# current_mirror.net
KiCad netlist of a schematic drawn in EAGLE
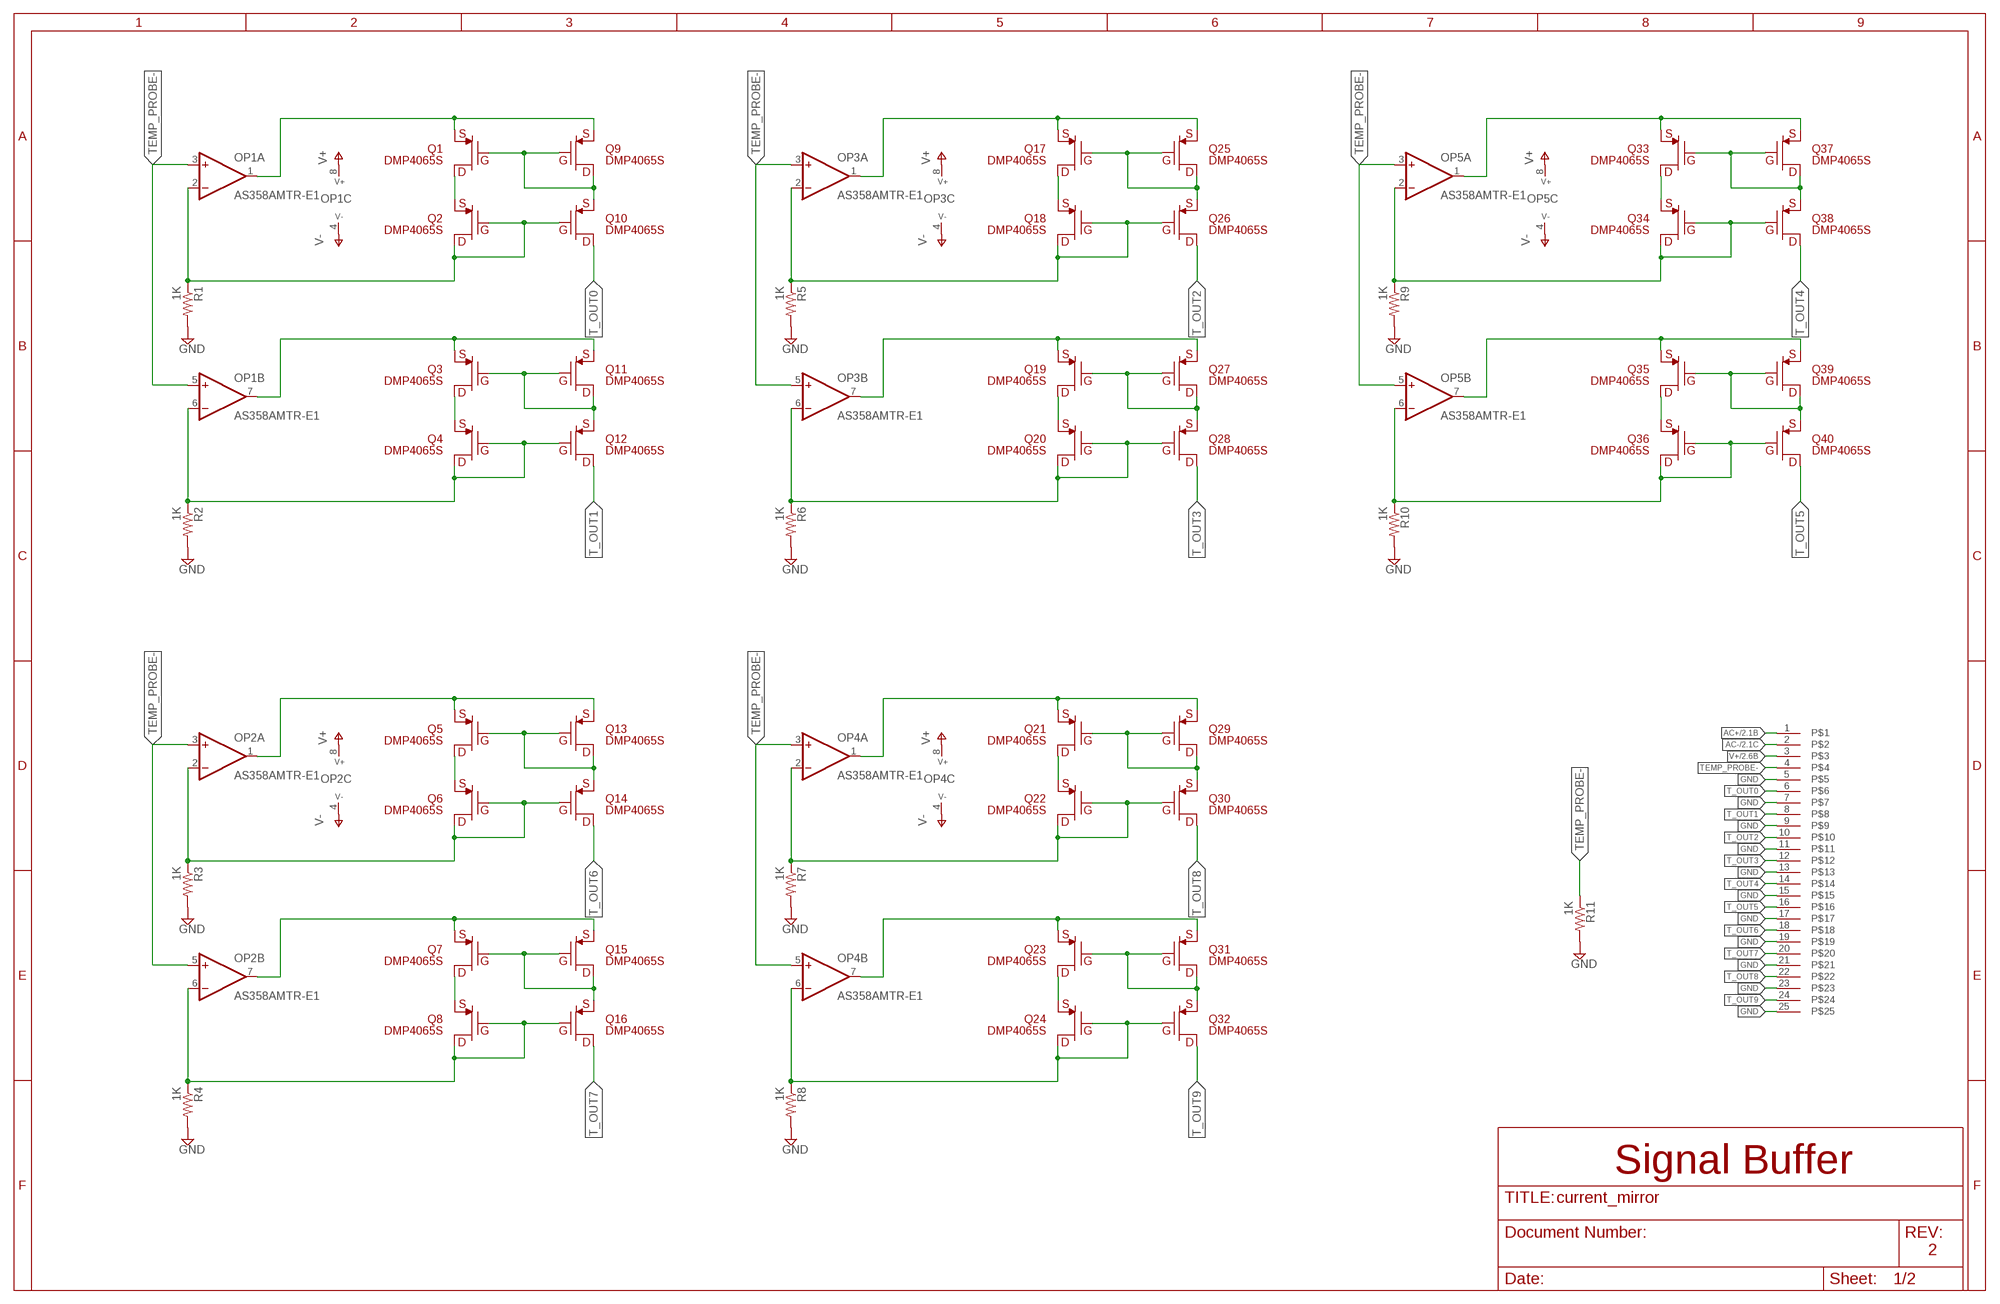
[diagram p0: schematic, sheet 1]
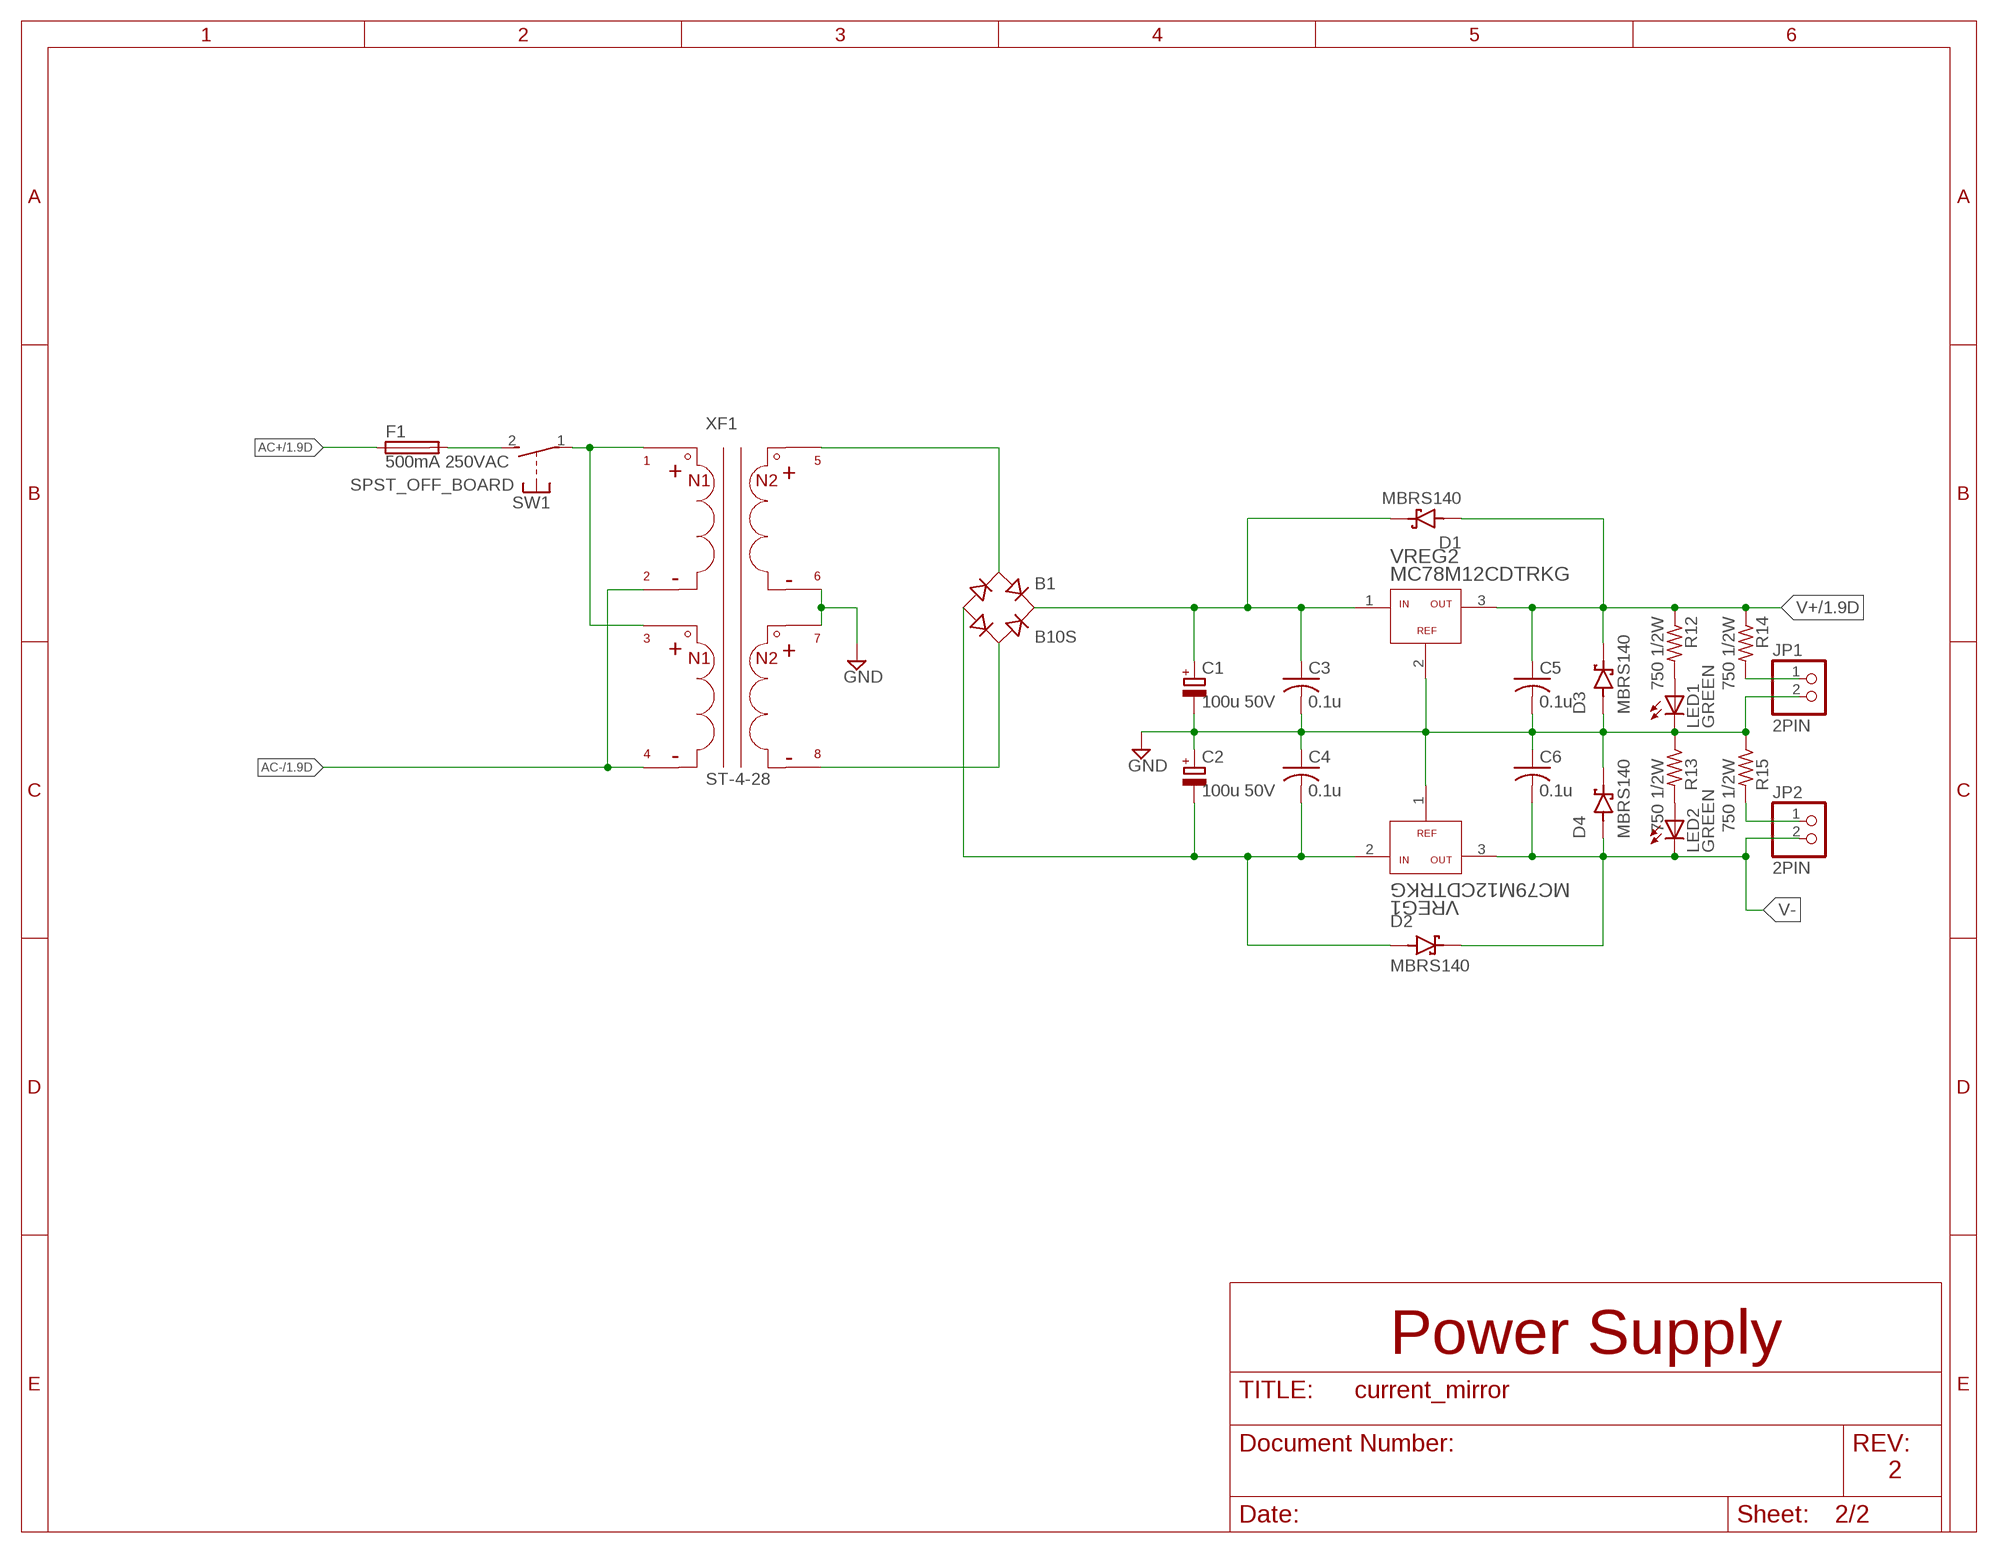
[diagram p1: schematic, sheet 2]

(export (version "E")
  (design (tool "Eeschema 10.0.6"))
  (components
    (comp (ref "J1")
      (value "2-282836-6")
      (footprint "eagle-import:SCREW_TERMINAL_25")
      (libsource (lib "eagle-import") (part "2-282836-6"))
    )
    (comp (ref "OP1")
      (value "AS358AMTR-E1")
      (footprint "eagle-import:SOIC-8")
      (fields (field (name "JLCPCB_PART_NUMBER") "C141322"))
      (libsource (lib "eagle-import") (part "AS358AMTR-E1"))
    )
    (comp (ref "OP2")
      (value "AS358AMTR-E1")
      (footprint "eagle-import:SOIC-8")
      (fields (field (name "JLCPCB_PART_NUMBER") "C141322"))
      (libsource (lib "eagle-import") (part "AS358AMTR-E1"))
    )
    (comp (ref "OP3")
      (value "AS358AMTR-E1")
      (footprint "eagle-import:SOIC-8")
      (fields (field (name "JLCPCB_PART_NUMBER") "C141322"))
      (libsource (lib "eagle-import") (part "AS358AMTR-E1"))
    )
    (comp (ref "OP4")
      (value "AS358AMTR-E1")
      (footprint "eagle-import:SOIC-8")
      (fields (field (name "JLCPCB_PART_NUMBER") "C141322"))
      (libsource (lib "eagle-import") (part "AS358AMTR-E1"))
    )
    (comp (ref "OP5")
      (value "AS358AMTR-E1")
      (footprint "eagle-import:SOIC-8")
      (fields (field (name "JLCPCB_PART_NUMBER") "C141322"))
      (libsource (lib "eagle-import") (part "AS358AMTR-E1"))
    )
    (comp (ref "Q1")
      (value "DMP4065S")
      (footprint "eagle-import:SOT23")
      (fields (field (name "JLCPCB_PART_NUMBER") "C182476"))
      (libsource (lib "eagle-import") (part "DMP4065S"))
    )
    (comp (ref "Q2")
      (value "DMP4065S")
      (footprint "eagle-import:SOT23")
      (fields (field (name "JLCPCB_PART_NUMBER") "C182476"))
      (libsource (lib "eagle-import") (part "DMP4065S"))
    )
    (comp (ref "Q3")
      (value "DMP4065S")
      (footprint "eagle-import:SOT23")
      (fields (field (name "JLCPCB_PART_NUMBER") "C182476"))
      (libsource (lib "eagle-import") (part "DMP4065S"))
    )
    (comp (ref "Q4")
      (value "DMP4065S")
      (footprint "eagle-import:SOT23")
      (fields (field (name "JLCPCB_PART_NUMBER") "C182476"))
      (libsource (lib "eagle-import") (part "DMP4065S"))
    )
    (comp (ref "Q5")
      (value "DMP4065S")
      (footprint "eagle-import:SOT23")
      (fields (field (name "JLCPCB_PART_NUMBER") "C182476"))
      (libsource (lib "eagle-import") (part "DMP4065S"))
    )
    (comp (ref "Q6")
      (value "DMP4065S")
      (footprint "eagle-import:SOT23")
      (fields (field (name "JLCPCB_PART_NUMBER") "C182476"))
      (libsource (lib "eagle-import") (part "DMP4065S"))
    )
    (comp (ref "Q7")
      (value "DMP4065S")
      (footprint "eagle-import:SOT23")
      (fields (field (name "JLCPCB_PART_NUMBER") "C182476"))
      (libsource (lib "eagle-import") (part "DMP4065S"))
    )
    (comp (ref "Q8")
      (value "DMP4065S")
      (footprint "eagle-import:SOT23")
      (fields (field (name "JLCPCB_PART_NUMBER") "C182476"))
      (libsource (lib "eagle-import") (part "DMP4065S"))
    )
    (comp (ref "Q9")
      (value "DMP4065S")
      (footprint "eagle-import:SOT23")
      (fields (field (name "JLCPCB_PART_NUMBER") "C182476"))
      (libsource (lib "eagle-import") (part "DMP4065S"))
    )
    (comp (ref "Q10")
      (value "DMP4065S")
      (footprint "eagle-import:SOT23")
      (fields (field (name "JLCPCB_PART_NUMBER") "C182476"))
      (libsource (lib "eagle-import") (part "DMP4065S"))
    )
    (comp (ref "Q11")
      (value "DMP4065S")
      (footprint "eagle-import:SOT23")
      (fields (field (name "JLCPCB_PART_NUMBER") "C182476"))
      (libsource (lib "eagle-import") (part "DMP4065S"))
    )
    (comp (ref "Q12")
      (value "DMP4065S")
      (footprint "eagle-import:SOT23")
      (fields (field (name "JLCPCB_PART_NUMBER") "C182476"))
      (libsource (lib "eagle-import") (part "DMP4065S"))
    )
    (comp (ref "Q13")
      (value "DMP4065S")
      (footprint "eagle-import:SOT23")
      (fields (field (name "JLCPCB_PART_NUMBER") "C182476"))
      (libsource (lib "eagle-import") (part "DMP4065S"))
    )
    (comp (ref "Q14")
      (value "DMP4065S")
      (footprint "eagle-import:SOT23")
      (fields (field (name "JLCPCB_PART_NUMBER") "C182476"))
      (libsource (lib "eagle-import") (part "DMP4065S"))
    )
    (comp (ref "Q15")
      (value "DMP4065S")
      (footprint "eagle-import:SOT23")
      (fields (field (name "JLCPCB_PART_NUMBER") "C182476"))
      (libsource (lib "eagle-import") (part "DMP4065S"))
    )
    (comp (ref "Q16")
      (value "DMP4065S")
      (footprint "eagle-import:SOT23")
      (fields (field (name "JLCPCB_PART_NUMBER") "C182476"))
      (libsource (lib "eagle-import") (part "DMP4065S"))
    )
    (comp (ref "Q17")
      (value "DMP4065S")
      (footprint "eagle-import:SOT23")
      (fields (field (name "JLCPCB_PART_NUMBER") "C182476"))
      (libsource (lib "eagle-import") (part "DMP4065S"))
    )
    (comp (ref "Q18")
      (value "DMP4065S")
      (footprint "eagle-import:SOT23")
      (fields (field (name "JLCPCB_PART_NUMBER") "C182476"))
      (libsource (lib "eagle-import") (part "DMP4065S"))
    )
    (comp (ref "Q19")
      (value "DMP4065S")
      (footprint "eagle-import:SOT23")
      (fields (field (name "JLCPCB_PART_NUMBER") "C182476"))
      (libsource (lib "eagle-import") (part "DMP4065S"))
    )
    (comp (ref "Q20")
      (value "DMP4065S")
      (footprint "eagle-import:SOT23")
      (fields (field (name "JLCPCB_PART_NUMBER") "C182476"))
      (libsource (lib "eagle-import") (part "DMP4065S"))
    )
    (comp (ref "Q21")
      (value "DMP4065S")
      (footprint "eagle-import:SOT23")
      (fields (field (name "JLCPCB_PART_NUMBER") "C182476"))
      (libsource (lib "eagle-import") (part "DMP4065S"))
    )
    (comp (ref "Q22")
      (value "DMP4065S")
      (footprint "eagle-import:SOT23")
      (fields (field (name "JLCPCB_PART_NUMBER") "C182476"))
      (libsource (lib "eagle-import") (part "DMP4065S"))
    )
    (comp (ref "Q23")
      (value "DMP4065S")
      (footprint "eagle-import:SOT23")
      (fields (field (name "JLCPCB_PART_NUMBER") "C182476"))
      (libsource (lib "eagle-import") (part "DMP4065S"))
    )
    (comp (ref "Q24")
      (value "DMP4065S")
      (footprint "eagle-import:SOT23")
      (fields (field (name "JLCPCB_PART_NUMBER") "C182476"))
      (libsource (lib "eagle-import") (part "DMP4065S"))
    )
    (comp (ref "Q25")
      (value "DMP4065S")
      (footprint "eagle-import:SOT23")
      (fields (field (name "JLCPCB_PART_NUMBER") "C182476"))
      (libsource (lib "eagle-import") (part "DMP4065S"))
    )
    (comp (ref "Q26")
      (value "DMP4065S")
      (footprint "eagle-import:SOT23")
      (fields (field (name "JLCPCB_PART_NUMBER") "C182476"))
      (libsource (lib "eagle-import") (part "DMP4065S"))
    )
    (comp (ref "Q27")
      (value "DMP4065S")
      (footprint "eagle-import:SOT23")
      (fields (field (name "JLCPCB_PART_NUMBER") "C182476"))
      (libsource (lib "eagle-import") (part "DMP4065S"))
    )
    (comp (ref "Q28")
      (value "DMP4065S")
      (footprint "eagle-import:SOT23")
      (fields (field (name "JLCPCB_PART_NUMBER") "C182476"))
      (libsource (lib "eagle-import") (part "DMP4065S"))
    )
    (comp (ref "Q29")
      (value "DMP4065S")
      (footprint "eagle-import:SOT23")
      (fields (field (name "JLCPCB_PART_NUMBER") "C182476"))
      (libsource (lib "eagle-import") (part "DMP4065S"))
    )
    (comp (ref "Q30")
      (value "DMP4065S")
      (footprint "eagle-import:SOT23")
      (fields (field (name "JLCPCB_PART_NUMBER") "C182476"))
      (libsource (lib "eagle-import") (part "DMP4065S"))
    )
    (comp (ref "Q31")
      (value "DMP4065S")
      (footprint "eagle-import:SOT23")
      (fields (field (name "JLCPCB_PART_NUMBER") "C182476"))
      (libsource (lib "eagle-import") (part "DMP4065S"))
    )
    (comp (ref "Q32")
      (value "DMP4065S")
      (footprint "eagle-import:SOT23")
      (fields (field (name "JLCPCB_PART_NUMBER") "C182476"))
      (libsource (lib "eagle-import") (part "DMP4065S"))
    )
    (comp (ref "Q33")
      (value "DMP4065S")
      (footprint "eagle-import:SOT23")
      (fields (field (name "JLCPCB_PART_NUMBER") "C182476"))
      (libsource (lib "eagle-import") (part "DMP4065S"))
    )
    (comp (ref "Q34")
      (value "DMP4065S")
      (footprint "eagle-import:SOT23")
      (fields (field (name "JLCPCB_PART_NUMBER") "C182476"))
      (libsource (lib "eagle-import") (part "DMP4065S"))
    )
    (comp (ref "Q35")
      (value "DMP4065S")
      (footprint "eagle-import:SOT23")
      (fields (field (name "JLCPCB_PART_NUMBER") "C182476"))
      (libsource (lib "eagle-import") (part "DMP4065S"))
    )
    (comp (ref "Q36")
      (value "DMP4065S")
      (footprint "eagle-import:SOT23")
      (fields (field (name "JLCPCB_PART_NUMBER") "C182476"))
      (libsource (lib "eagle-import") (part "DMP4065S"))
    )
    (comp (ref "Q37")
      (value "DMP4065S")
      (footprint "eagle-import:SOT23")
      (fields (field (name "JLCPCB_PART_NUMBER") "C182476"))
      (libsource (lib "eagle-import") (part "DMP4065S"))
    )
    (comp (ref "Q38")
      (value "DMP4065S")
      (footprint "eagle-import:SOT23")
      (fields (field (name "JLCPCB_PART_NUMBER") "C182476"))
      (libsource (lib "eagle-import") (part "DMP4065S"))
    )
    (comp (ref "Q39")
      (value "DMP4065S")
      (footprint "eagle-import:SOT23")
      (fields (field (name "JLCPCB_PART_NUMBER") "C182476"))
      (libsource (lib "eagle-import") (part "DMP4065S"))
    )
    (comp (ref "Q40")
      (value "DMP4065S")
      (footprint "eagle-import:SOT23")
      (fields (field (name "JLCPCB_PART_NUMBER") "C182476"))
      (libsource (lib "eagle-import") (part "DMP4065S"))
    )
    (comp (ref "R1")
      (value "1K")
      (footprint "eagle-import:R1206")
      (libsource (lib "eagle-import") (part "R-US_R1206"))
    )
    (comp (ref "R2")
      (value "1K")
      (footprint "eagle-import:R1206")
      (libsource (lib "eagle-import") (part "R-US_R1206"))
    )
    (comp (ref "R3")
      (value "1K")
      (footprint "eagle-import:R1206")
      (libsource (lib "eagle-import") (part "R-US_R1206"))
    )
    (comp (ref "R4")
      (value "1K")
      (footprint "eagle-import:R1206")
      (libsource (lib "eagle-import") (part "R-US_R1206"))
    )
    (comp (ref "R5")
      (value "1K")
      (footprint "eagle-import:R1206")
      (libsource (lib "eagle-import") (part "R-US_R1206"))
    )
    (comp (ref "R6")
      (value "1K")
      (footprint "eagle-import:R1206")
      (libsource (lib "eagle-import") (part "R-US_R1206"))
    )
    (comp (ref "R7")
      (value "1K")
      (footprint "eagle-import:R1206")
      (libsource (lib "eagle-import") (part "R-US_R1206"))
    )
    (comp (ref "R8")
      (value "1K")
      (footprint "eagle-import:R1206")
      (libsource (lib "eagle-import") (part "R-US_R1206"))
    )
    (comp (ref "R9")
      (value "1K")
      (footprint "eagle-import:R1206")
      (libsource (lib "eagle-import") (part "R-US_R1206"))
    )
    (comp (ref "R10")
      (value "1K")
      (footprint "eagle-import:R1206")
      (libsource (lib "eagle-import") (part "R-US_R1206"))
    )
    (comp (ref "R11")
      (value "1K")
      (footprint "eagle-import:R1206")
      (libsource (lib "eagle-import") (part "R-US_R1206"))
    )
    (comp (ref "B1")
      (value "B10S")
      (footprint "eagle-import:MBS")
      (libsource (lib "eagle-import") (part "BS10"))
    )
    (comp (ref "C1")
      (value "100u 50V")
      (footprint "eagle-import:153CLV-1010")
      (libsource (lib "eagle-import") (part "CPOL-EU153CLV-1010"))
    )
    (comp (ref "C2")
      (value "100u 50V")
      (footprint "eagle-import:153CLV-1010")
      (libsource (lib "eagle-import") (part "CPOL-EU153CLV-1010"))
    )
    (comp (ref "C3")
      (value "0.1u")
      (footprint "eagle-import:C0603")
      (libsource (lib "eagle-import") (part "C-USC0603"))
    )
    (comp (ref "C4")
      (value "0.1u")
      (footprint "eagle-import:C0603")
      (libsource (lib "eagle-import") (part "C-USC0603"))
    )
    (comp (ref "C5")
      (value "0.1u")
      (footprint "eagle-import:C0603")
      (libsource (lib "eagle-import") (part "C-USC0603"))
    )
    (comp (ref "C6")
      (value "0.1u")
      (footprint "eagle-import:C0603")
      (libsource (lib "eagle-import") (part "C-USC0603"))
    )
    (comp (ref "D1")
      (value "MBRS140")
      (footprint "eagle-import:DIO_MBRS140")
      (fields
        (field (name "DIGI-KEY_PART_NUMBER") "MBRS140FSCT-ND")
        (field (name "JLCPCB_PART_NUMBER") "C133091")
        (field (name "MF") "ON Semiconductor")
      )
      (libsource (lib "eagle-import") (part "MBRS140"))
    )
    (comp (ref "D2")
      (value "MBRS140")
      (footprint "eagle-import:DIO_MBRS140")
      (fields
        (field (name "DIGI-KEY_PART_NUMBER") "MBRS140FSCT-ND")
        (field (name "JLCPCB_PART_NUMBER") "C133091")
        (field (name "MF") "ON Semiconductor")
      )
      (libsource (lib "eagle-import") (part "MBRS140"))
    )
    (comp (ref "D3")
      (value "MBRS140")
      (footprint "eagle-import:DIO_MBRS140")
      (fields
        (field (name "DIGI-KEY_PART_NUMBER") "MBRS140FSCT-ND")
        (field (name "JLCPCB_PART_NUMBER") "C133091")
        (field (name "MF") "ON Semiconductor")
      )
      (libsource (lib "eagle-import") (part "MBRS140"))
    )
    (comp (ref "D4")
      (value "MBRS140")
      (footprint "eagle-import:DIO_MBRS140")
      (fields
        (field (name "DIGI-KEY_PART_NUMBER") "MBRS140FSCT-ND")
        (field (name "JLCPCB_PART_NUMBER") "C133091")
        (field (name "MF") "ON Semiconductor")
      )
      (libsource (lib "eagle-import") (part "MBRS140"))
    )
    (comp (ref "F1")
      (value "500mA 250VAC")
      (footprint "eagle-import:SH22")
      (libsource (lib "eagle-import") (part "SH22"))
    )
    (comp (ref "JP1")
      (value "2PIN")
      (footprint "eagle-import:1X02")
      (libsource (lib "eagle-import") (part "PINHD-1X2"))
    )
    (comp (ref "JP2")
      (value "2PIN")
      (footprint "eagle-import:1X02")
      (libsource (lib "eagle-import") (part "PINHD-1X2"))
    )
    (comp (ref "LED1")
      (value "GREEN")
      (footprint "eagle-import:CHIP-LED0603")
      (libsource (lib "eagle-import") (part "LEDCHIP-LED0603"))
    )
    (comp (ref "LED2")
      (value "GREEN")
      (footprint "eagle-import:CHIP-LED0603")
      (libsource (lib "eagle-import") (part "LEDCHIP-LED0603"))
    )
    (comp (ref "R12")
      (value "750 1/2W")
      (footprint "eagle-import:R1206")
      (libsource (lib "eagle-import") (part "R-US_R1206"))
    )
    (comp (ref "R13")
      (value "750 1/2W")
      (footprint "eagle-import:R1206")
      (libsource (lib "eagle-import") (part "R-US_R1206"))
    )
    (comp (ref "R14")
      (value "750 1/2W")
      (footprint "eagle-import:R1206")
      (libsource (lib "eagle-import") (part "R-US_R1206"))
    )
    (comp (ref "R15")
      (value "750 1/2W")
      (footprint "eagle-import:R1206")
      (libsource (lib "eagle-import") (part "R-US_R1206"))
    )
    (comp (ref "SW1")
      (value "SPST_OFF_BOARD")
      (footprint "eagle-import:SPST_OFF_BOARD")
      (libsource (lib "eagle-import") (part "SPST_OFF_BOARD"))
    )
    (comp (ref "VREG1")
      (value "MC79M12CDTRKG")
      (footprint "eagle-import:DPAK-3")
      (fields (field (name "JLCPCB_PART_NUMBER") "C67852"))
      (libsource (lib "eagle-import") (part "MC79M12CDTRKG"))
    )
    (comp (ref "VREG2")
      (value "MC78M12CDTRKG")
      (footprint "eagle-import:DPAK-3")
      (fields
        (field (name "JLCPCB_PART_NUMBER") "C67851")
        (field (name "COPYRIGHT") "Copyright (C) 2016 Accelerated Designs. All rights reserved")
      )
      (libsource (lib "eagle-import") (part "MC78M12CDTRKG"))
    )
    (comp (ref "XF1")
      (value "ST-4-28")
      (footprint "eagle-import:ST-4-28")
      (libsource (lib "eagle-import") (part "ST-4-28"))
    )
  )
  (nets
    (net (code "1") (name "AC+") (class "Default")
      (node (ref "F1") (pin "1") (pinfunction "1_1") (pintype "passive"))
      (node (ref "J1") (pin "1") (pinfunction "P$1_1") (pintype "bidirectional"))
    )
    (net (code "2") (name "AC-") (class "Default")
      (node (ref "J1") (pin "2") (pinfunction "P$2_2") (pintype "bidirectional"))
      (node (ref "XF1") (pin "P$2") (pinfunction "P$2_P$2") (pintype "bidirectional"))
      (node (ref "XF1") (pin "P$4") (pinfunction "P$4_P$4") (pintype "bidirectional"))
    )
    (net (code "3") (name "GND") (class "Default")
      (node (ref "C1") (pin "-") (pinfunction "-_-") (pintype "passive"))
      (node (ref "C2") (pin "+") (pinfunction "+_+") (pintype "passive"))
      (node (ref "C3") (pin "2") (pinfunction "2_2") (pintype "passive"))
      (node (ref "C4") (pin "1") (pinfunction "1_1") (pintype "passive"))
      (node (ref "C5") (pin "2") (pinfunction "2_2") (pintype "passive"))
      (node (ref "C6") (pin "1") (pinfunction "1_1") (pintype "passive"))
      (node (ref "D3") (pin "A") (pinfunction "A_A") (pintype "passive"))
      (node (ref "D4") (pin "C") (pinfunction "K_C") (pintype "passive"))
      (node (ref "J1") (pin "11") (pinfunction "P$11_11") (pintype "bidirectional"))
      (node (ref "J1") (pin "13") (pinfunction "P$13_13") (pintype "bidirectional"))
      (node (ref "J1") (pin "15") (pinfunction "P$15_15") (pintype "bidirectional"))
      (node (ref "J1") (pin "17") (pinfunction "P$17_17") (pintype "bidirectional"))
      (node (ref "J1") (pin "19") (pinfunction "P$19_19") (pintype "bidirectional"))
      (node (ref "J1") (pin "21") (pinfunction "P$21_21") (pintype "bidirectional"))
      (node (ref "J1") (pin "23") (pinfunction "P$23_23") (pintype "bidirectional"))
      (node (ref "J1") (pin "25") (pinfunction "P$25_25") (pintype "bidirectional"))
      (node (ref "J1") (pin "5") (pinfunction "P$5_5") (pintype "bidirectional"))
      (node (ref "J1") (pin "7") (pinfunction "P$7_7") (pintype "bidirectional"))
      (node (ref "J1") (pin "9") (pinfunction "P$9_9") (pintype "bidirectional"))
      (node (ref "JP1") (pin "2") (pinfunction "2_2") (pintype "passive"))
      (node (ref "LED1") (pin "C") (pinfunction "C_C") (pintype "passive"))
      (node (ref "R1") (pin "2") (pinfunction "2_2") (pintype "passive"))
      (node (ref "R10") (pin "2") (pinfunction "2_2") (pintype "passive"))
      (node (ref "R11") (pin "2") (pinfunction "2_2") (pintype "passive"))
      (node (ref "R13") (pin "1") (pinfunction "1_1") (pintype "passive"))
      (node (ref "R15") (pin "1") (pinfunction "1_1") (pintype "passive"))
      (node (ref "R2") (pin "2") (pinfunction "2_2") (pintype "passive"))
      (node (ref "R3") (pin "2") (pinfunction "2_2") (pintype "passive"))
      (node (ref "R4") (pin "2") (pinfunction "2_2") (pintype "passive"))
      (node (ref "R5") (pin "2") (pinfunction "2_2") (pintype "passive"))
      (node (ref "R6") (pin "2") (pinfunction "2_2") (pintype "passive"))
      (node (ref "R7") (pin "2") (pinfunction "2_2") (pintype "passive"))
      (node (ref "R8") (pin "2") (pinfunction "2_2") (pintype "passive"))
      (node (ref "R9") (pin "2") (pinfunction "2_2") (pintype "passive"))
      (node (ref "VREG1") (pin "1") (pinfunction "GND_1") (pintype "power_in"))
      (node (ref "VREG2") (pin "2") (pinfunction "GND_2") (pintype "power_in"))
      (node (ref "XF1") (pin "P$6") (pinfunction "P$6_P$6") (pintype "bidirectional"))
      (node (ref "XF1") (pin "P$7") (pinfunction "P$7_P$7") (pintype "bidirectional"))
    )
    (net (code "4") (name "Net-(B1-PadAC1)") (class "Default")
      (node (ref "B1") (pin "AC1") (pinfunction "AC1_AC1") (pintype "passive"))
      (node (ref "XF1") (pin "P$5") (pinfunction "P$5_P$5") (pintype "bidirectional"))
    )
    (net (code "5") (name "Net-(B1-PadAC2)") (class "Default")
      (node (ref "B1") (pin "AC2") (pinfunction "AC2_AC2") (pintype "passive"))
      (node (ref "XF1") (pin "P$8") (pinfunction "P$8_P$8") (pintype "bidirectional"))
    )
    (net (code "6") (name "Net-(D1-K)") (class "Default")
      (node (ref "B1") (pin "+") (pinfunction "+_+") (pintype "passive"))
      (node (ref "C1") (pin "+") (pinfunction "+_+") (pintype "passive"))
      (node (ref "C3") (pin "1") (pinfunction "1_1") (pintype "passive"))
      (node (ref "D1") (pin "C") (pinfunction "K_C") (pintype "passive"))
      (node (ref "VREG2") (pin "1") (pinfunction "VIN_1") (pintype "power_in"))
    )
    (net (code "7") (name "Net-(JP1-Pad1)") (class "Default")
      (node (ref "JP1") (pin "1") (pinfunction "1_1") (pintype "passive"))
      (node (ref "R14") (pin "2") (pinfunction "2_2") (pintype "passive"))
    )
    (net (code "8") (name "Net-(JP2-Pad1)") (class "Default")
      (node (ref "JP2") (pin "1") (pinfunction "1_1") (pintype "passive"))
      (node (ref "R15") (pin "2") (pinfunction "2_2") (pintype "passive"))
    )
    (net (code "9") (name "Net-(LED1-PadA)") (class "Default")
      (node (ref "LED1") (pin "A") (pinfunction "A_A") (pintype "passive"))
      (node (ref "R12") (pin "2") (pinfunction "2_2") (pintype "passive"))
    )
    (net (code "10") (name "Net-(LED2-PadA)") (class "Default")
      (node (ref "LED2") (pin "A") (pinfunction "A_A") (pintype "passive"))
      (node (ref "R13") (pin "2") (pinfunction "2_2") (pintype "passive"))
    )
    (net (code "11") (name "Net-(OP1A--IN)") (class "Default")
      (node (ref "OP1") (pin "2") (pinfunction "-IN_2") (pintype "bidirectional"))
      (node (ref "Q10") (pin "1") (pinfunction "G1_1") (pintype "passive"))
      (node (ref "Q2") (pin "1") (pinfunction "G1_1") (pintype "passive"))
      (node (ref "Q2") (pin "3") (pinfunction "D1_3") (pintype "passive"))
      (node (ref "R1") (pin "1") (pinfunction "1_1") (pintype "passive"))
    )
    (net (code "12") (name "Net-(OP1A-OUT)") (class "Default")
      (node (ref "OP1") (pin "1") (pinfunction "OUT_1") (pintype "output"))
      (node (ref "Q1") (pin "2") (pinfunction "S1_2") (pintype "passive"))
      (node (ref "Q9") (pin "2") (pinfunction "S1_2") (pintype "passive"))
    )
    (net (code "13") (name "Net-(OP1B--IN)") (class "Default")
      (node (ref "OP1") (pin "6") (pinfunction "-IN_6") (pintype "bidirectional"))
      (node (ref "Q12") (pin "1") (pinfunction "G1_1") (pintype "passive"))
      (node (ref "Q4") (pin "1") (pinfunction "G1_1") (pintype "passive"))
      (node (ref "Q4") (pin "3") (pinfunction "D1_3") (pintype "passive"))
      (node (ref "R2") (pin "1") (pinfunction "1_1") (pintype "passive"))
    )
    (net (code "14") (name "Net-(OP1B-OUT)") (class "Default")
      (node (ref "OP1") (pin "7") (pinfunction "OUT_7") (pintype "output"))
      (node (ref "Q11") (pin "2") (pinfunction "S1_2") (pintype "passive"))
      (node (ref "Q3") (pin "2") (pinfunction "S1_2") (pintype "passive"))
    )
    (net (code "15") (name "Net-(OP2A--IN)") (class "Default")
      (node (ref "OP2") (pin "2") (pinfunction "-IN_2") (pintype "bidirectional"))
      (node (ref "Q14") (pin "1") (pinfunction "G1_1") (pintype "passive"))
      (node (ref "Q6") (pin "1") (pinfunction "G1_1") (pintype "passive"))
      (node (ref "Q6") (pin "3") (pinfunction "D1_3") (pintype "passive"))
      (node (ref "R3") (pin "1") (pinfunction "1_1") (pintype "passive"))
    )
    (net (code "16") (name "Net-(OP2A-OUT)") (class "Default")
      (node (ref "OP2") (pin "1") (pinfunction "OUT_1") (pintype "output"))
      (node (ref "Q13") (pin "2") (pinfunction "S1_2") (pintype "passive"))
      (node (ref "Q5") (pin "2") (pinfunction "S1_2") (pintype "passive"))
    )
    (net (code "17") (name "Net-(OP2B--IN)") (class "Default")
      (node (ref "OP2") (pin "6") (pinfunction "-IN_6") (pintype "bidirectional"))
      (node (ref "Q16") (pin "1") (pinfunction "G1_1") (pintype "passive"))
      (node (ref "Q8") (pin "1") (pinfunction "G1_1") (pintype "passive"))
      (node (ref "Q8") (pin "3") (pinfunction "D1_3") (pintype "passive"))
      (node (ref "R4") (pin "1") (pinfunction "1_1") (pintype "passive"))
    )
    (net (code "18") (name "Net-(OP2B-OUT)") (class "Default")
      (node (ref "OP2") (pin "7") (pinfunction "OUT_7") (pintype "output"))
      (node (ref "Q15") (pin "2") (pinfunction "S1_2") (pintype "passive"))
      (node (ref "Q7") (pin "2") (pinfunction "S1_2") (pintype "passive"))
    )
    (net (code "19") (name "Net-(OP3A--IN)") (class "Default")
      (node (ref "OP3") (pin "2") (pinfunction "-IN_2") (pintype "bidirectional"))
      (node (ref "Q18") (pin "1") (pinfunction "G1_1") (pintype "passive"))
      (node (ref "Q18") (pin "3") (pinfunction "D1_3") (pintype "passive"))
      (node (ref "Q26") (pin "1") (pinfunction "G1_1") (pintype "passive"))
      (node (ref "R5") (pin "1") (pinfunction "1_1") (pintype "passive"))
    )
    (net (code "20") (name "Net-(OP3A-OUT)") (class "Default")
      (node (ref "OP3") (pin "1") (pinfunction "OUT_1") (pintype "output"))
      (node (ref "Q17") (pin "2") (pinfunction "S1_2") (pintype "passive"))
      (node (ref "Q25") (pin "2") (pinfunction "S1_2") (pintype "passive"))
    )
    (net (code "21") (name "Net-(OP3B--IN)") (class "Default")
      (node (ref "OP3") (pin "6") (pinfunction "-IN_6") (pintype "bidirectional"))
      (node (ref "Q20") (pin "1") (pinfunction "G1_1") (pintype "passive"))
      (node (ref "Q20") (pin "3") (pinfunction "D1_3") (pintype "passive"))
      (node (ref "Q28") (pin "1") (pinfunction "G1_1") (pintype "passive"))
      (node (ref "R6") (pin "1") (pinfunction "1_1") (pintype "passive"))
    )
    (net (code "22") (name "Net-(OP3B-OUT)") (class "Default")
      (node (ref "OP3") (pin "7") (pinfunction "OUT_7") (pintype "output"))
      (node (ref "Q19") (pin "2") (pinfunction "S1_2") (pintype "passive"))
      (node (ref "Q27") (pin "2") (pinfunction "S1_2") (pintype "passive"))
    )
    (net (code "23") (name "Net-(OP4A--IN)") (class "Default")
      (node (ref "OP4") (pin "2") (pinfunction "-IN_2") (pintype "bidirectional"))
      (node (ref "Q22") (pin "1") (pinfunction "G1_1") (pintype "passive"))
      (node (ref "Q22") (pin "3") (pinfunction "D1_3") (pintype "passive"))
      (node (ref "Q30") (pin "1") (pinfunction "G1_1") (pintype "passive"))
      (node (ref "R7") (pin "1") (pinfunction "1_1") (pintype "passive"))
    )
    (net (code "24") (name "Net-(OP4A-OUT)") (class "Default")
      (node (ref "OP4") (pin "1") (pinfunction "OUT_1") (pintype "output"))
      (node (ref "Q21") (pin "2") (pinfunction "S1_2") (pintype "passive"))
      (node (ref "Q29") (pin "2") (pinfunction "S1_2") (pintype "passive"))
    )
    (net (code "25") (name "Net-(OP4B--IN)") (class "Default")
      (node (ref "OP4") (pin "6") (pinfunction "-IN_6") (pintype "bidirectional"))
      (node (ref "Q24") (pin "1") (pinfunction "G1_1") (pintype "passive"))
      (node (ref "Q24") (pin "3") (pinfunction "D1_3") (pintype "passive"))
      (node (ref "Q32") (pin "1") (pinfunction "G1_1") (pintype "passive"))
      (node (ref "R8") (pin "1") (pinfunction "1_1") (pintype "passive"))
    )
    (net (code "26") (name "Net-(OP4B-OUT)") (class "Default")
      (node (ref "OP4") (pin "7") (pinfunction "OUT_7") (pintype "output"))
      (node (ref "Q23") (pin "2") (pinfunction "S1_2") (pintype "passive"))
      (node (ref "Q31") (pin "2") (pinfunction "S1_2") (pintype "passive"))
    )
    (net (code "27") (name "Net-(OP5A--IN)") (class "Default")
      (node (ref "OP5") (pin "2") (pinfunction "-IN_2") (pintype "bidirectional"))
      (node (ref "Q34") (pin "1") (pinfunction "G1_1") (pintype "passive"))
      (node (ref "Q34") (pin "3") (pinfunction "D1_3") (pintype "passive"))
      (node (ref "Q38") (pin "1") (pinfunction "G1_1") (pintype "passive"))
      (node (ref "R9") (pin "1") (pinfunction "1_1") (pintype "passive"))
    )
    (net (code "28") (name "Net-(OP5A-OUT)") (class "Default")
      (node (ref "OP5") (pin "1") (pinfunction "OUT_1") (pintype "output"))
      (node (ref "Q33") (pin "2") (pinfunction "S1_2") (pintype "passive"))
      (node (ref "Q37") (pin "2") (pinfunction "S1_2") (pintype "passive"))
    )
    (net (code "29") (name "Net-(OP5B--IN)") (class "Default")
      (node (ref "OP5") (pin "6") (pinfunction "-IN_6") (pintype "bidirectional"))
      (node (ref "Q36") (pin "1") (pinfunction "G1_1") (pintype "passive"))
      (node (ref "Q36") (pin "3") (pinfunction "D1_3") (pintype "passive"))
      (node (ref "Q40") (pin "1") (pinfunction "G1_1") (pintype "passive"))
      (node (ref "R10") (pin "1") (pinfunction "1_1") (pintype "passive"))
    )
    (net (code "30") (name "Net-(OP5B-OUT)") (class "Default")
      (node (ref "OP5") (pin "7") (pinfunction "OUT_7") (pintype "output"))
      (node (ref "Q35") (pin "2") (pinfunction "S1_2") (pintype "passive"))
      (node (ref "Q39") (pin "2") (pinfunction "S1_2") (pintype "passive"))
    )
    (net (code "31") (name "Net-(Q1-D1)") (class "Default")
      (node (ref "Q1") (pin "3") (pinfunction "D1_3") (pintype "passive"))
      (node (ref "Q2") (pin "2") (pinfunction "S1_2") (pintype "passive"))
    )
    (net (code "32") (name "Net-(Q1-G1)") (class "Default")
      (node (ref "Q1") (pin "1") (pinfunction "G1_1") (pintype "passive"))
      (node (ref "Q10") (pin "2") (pinfunction "S1_2") (pintype "passive"))
      (node (ref "Q9") (pin "1") (pinfunction "G1_1") (pintype "passive"))
      (node (ref "Q9") (pin "3") (pinfunction "D1_3") (pintype "passive"))
    )
    (net (code "33") (name "Net-(Q3-D1)") (class "Default")
      (node (ref "Q3") (pin "3") (pinfunction "D1_3") (pintype "passive"))
      (node (ref "Q4") (pin "2") (pinfunction "S1_2") (pintype "passive"))
    )
    (net (code "34") (name "Net-(Q5-D1)") (class "Default")
      (node (ref "Q5") (pin "3") (pinfunction "D1_3") (pintype "passive"))
      (node (ref "Q6") (pin "2") (pinfunction "S1_2") (pintype "passive"))
    )
    (net (code "35") (name "Net-(Q7-D1)") (class "Default")
      (node (ref "Q7") (pin "3") (pinfunction "D1_3") (pintype "passive"))
      (node (ref "Q8") (pin "2") (pinfunction "S1_2") (pintype "passive"))
    )
    (net (code "36") (name "Net-(Q11-D1)") (class "Default")
      (node (ref "Q11") (pin "1") (pinfunction "G1_1") (pintype "passive"))
      (node (ref "Q11") (pin "3") (pinfunction "D1_3") (pintype "passive"))
      (node (ref "Q12") (pin "2") (pinfunction "S1_2") (pintype "passive"))
      (node (ref "Q3") (pin "1") (pinfunction "G1_1") (pintype "passive"))
    )
    (net (code "37") (name "Net-(Q13-D1)") (class "Default")
      (node (ref "Q13") (pin "1") (pinfunction "G1_1") (pintype "passive"))
      (node (ref "Q13") (pin "3") (pinfunction "D1_3") (pintype "passive"))
      (node (ref "Q14") (pin "2") (pinfunction "S1_2") (pintype "passive"))
      (node (ref "Q5") (pin "1") (pinfunction "G1_1") (pintype "passive"))
    )
    (net (code "38") (name "Net-(Q15-D1)") (class "Default")
      (node (ref "Q15") (pin "1") (pinfunction "G1_1") (pintype "passive"))
      (node (ref "Q15") (pin "3") (pinfunction "D1_3") (pintype "passive"))
      (node (ref "Q16") (pin "2") (pinfunction "S1_2") (pintype "passive"))
      (node (ref "Q7") (pin "1") (pinfunction "G1_1") (pintype "passive"))
    )
    (net (code "39") (name "Net-(Q17-D1)") (class "Default")
      (node (ref "Q17") (pin "3") (pinfunction "D1_3") (pintype "passive"))
      (node (ref "Q18") (pin "2") (pinfunction "S1_2") (pintype "passive"))
    )
    (net (code "40") (name "Net-(Q17-G1)") (class "Default")
      (node (ref "Q17") (pin "1") (pinfunction "G1_1") (pintype "passive"))
      (node (ref "Q25") (pin "1") (pinfunction "G1_1") (pintype "passive"))
      (node (ref "Q25") (pin "3") (pinfunction "D1_3") (pintype "passive"))
      (node (ref "Q26") (pin "2") (pinfunction "S1_2") (pintype "passive"))
    )
    (net (code "41") (name "Net-(Q19-D1)") (class "Default")
      (node (ref "Q19") (pin "3") (pinfunction "D1_3") (pintype "passive"))
      (node (ref "Q20") (pin "2") (pinfunction "S1_2") (pintype "passive"))
    )
    (net (code "42") (name "Net-(Q19-G1)") (class "Default")
      (node (ref "Q19") (pin "1") (pinfunction "G1_1") (pintype "passive"))
      (node (ref "Q27") (pin "1") (pinfunction "G1_1") (pintype "passive"))
      (node (ref "Q27") (pin "3") (pinfunction "D1_3") (pintype "passive"))
      (node (ref "Q28") (pin "2") (pinfunction "S1_2") (pintype "passive"))
    )
    (net (code "43") (name "Net-(Q21-D1)") (class "Default")
      (node (ref "Q21") (pin "3") (pinfunction "D1_3") (pintype "passive"))
      (node (ref "Q22") (pin "2") (pinfunction "S1_2") (pintype "passive"))
    )
    (net (code "44") (name "Net-(Q21-G1)") (class "Default")
      (node (ref "Q21") (pin "1") (pinfunction "G1_1") (pintype "passive"))
      (node (ref "Q29") (pin "1") (pinfunction "G1_1") (pintype "passive"))
      (node (ref "Q29") (pin "3") (pinfunction "D1_3") (pintype "passive"))
      (node (ref "Q30") (pin "2") (pinfunction "S1_2") (pintype "passive"))
    )
    (net (code "45") (name "Net-(Q23-D1)") (class "Default")
      (node (ref "Q23") (pin "3") (pinfunction "D1_3") (pintype "passive"))
      (node (ref "Q24") (pin "2") (pinfunction "S1_2") (pintype "passive"))
    )
    (net (code "46") (name "Net-(Q23-G1)") (class "Default")
      (node (ref "Q23") (pin "1") (pinfunction "G1_1") (pintype "passive"))
      (node (ref "Q31") (pin "1") (pinfunction "G1_1") (pintype "passive"))
      (node (ref "Q31") (pin "3") (pinfunction "D1_3") (pintype "passive"))
      (node (ref "Q32") (pin "2") (pinfunction "S1_2") (pintype "passive"))
    )
    (net (code "47") (name "Net-(Q33-D1)") (class "Default")
      (node (ref "Q33") (pin "3") (pinfunction "D1_3") (pintype "passive"))
      (node (ref "Q34") (pin "2") (pinfunction "S1_2") (pintype "passive"))
    )
    (net (code "48") (name "Net-(Q33-G1)") (class "Default")
      (node (ref "Q33") (pin "1") (pinfunction "G1_1") (pintype "passive"))
      (node (ref "Q37") (pin "1") (pinfunction "G1_1") (pintype "passive"))
      (node (ref "Q37") (pin "3") (pinfunction "D1_3") (pintype "passive"))
      (node (ref "Q38") (pin "2") (pinfunction "S1_2") (pintype "passive"))
    )
    (net (code "49") (name "Net-(Q35-D1)") (class "Default")
      (node (ref "Q35") (pin "3") (pinfunction "D1_3") (pintype "passive"))
      (node (ref "Q36") (pin "2") (pinfunction "S1_2") (pintype "passive"))
    )
    (net (code "50") (name "Net-(Q35-G1)") (class "Default")
      (node (ref "Q35") (pin "1") (pinfunction "G1_1") (pintype "passive"))
      (node (ref "Q39") (pin "1") (pinfunction "G1_1") (pintype "passive"))
      (node (ref "Q39") (pin "3") (pinfunction "D1_3") (pintype "passive"))
      (node (ref "Q40") (pin "2") (pinfunction "S1_2") (pintype "passive"))
    )
    (net (code "51") (name "Net-(SW1-P)") (class "Default")
      (node (ref "SW1") (pin "1") (pinfunction "P_1") (pintype "passive"))
      (node (ref "XF1") (pin "P$1") (pinfunction "P$1_P$1") (pintype "bidirectional"))
      (node (ref "XF1") (pin "P$3") (pinfunction "P$3_P$3") (pintype "bidirectional"))
    )
    (net (code "52") (name "Net-(SW1-S)") (class "Default")
      (node (ref "F1") (pin "2") (pinfunction "2_2") (pintype "passive"))
      (node (ref "SW1") (pin "2") (pinfunction "S_2") (pintype "passive"))
    )
    (net (code "53") (name "Net-(VREG1-VIN)") (class "Default")
      (node (ref "B1") (pin "-") (pinfunction "-_-") (pintype "passive"))
      (node (ref "C2") (pin "-") (pinfunction "-_-") (pintype "passive"))
      (node (ref "C4") (pin "2") (pinfunction "2_2") (pintype "passive"))
      (node (ref "D2") (pin "A") (pinfunction "A_A") (pintype "passive"))
      (node (ref "VREG1") (pin "2") (pinfunction "VIN_2") (pintype "power_in"))
    )
    (net (code "54") (name "TEMP_PROBE-") (class "Default")
      (node (ref "J1") (pin "4") (pinfunction "P$4_4") (pintype "bidirectional"))
      (node (ref "OP1") (pin "3") (pinfunction "+IN_3") (pintype "bidirectional"))
      (node (ref "OP1") (pin "5") (pinfunction "+IN_5") (pintype "bidirectional"))
      (node (ref "OP2") (pin "3") (pinfunction "+IN_3") (pintype "bidirectional"))
      (node (ref "OP2") (pin "5") (pinfunction "+IN_5") (pintype "bidirectional"))
      (node (ref "OP3") (pin "3") (pinfunction "+IN_3") (pintype "bidirectional"))
      (node (ref "OP3") (pin "5") (pinfunction "+IN_5") (pintype "bidirectional"))
      (node (ref "OP4") (pin "3") (pinfunction "+IN_3") (pintype "bidirectional"))
      (node (ref "OP4") (pin "5") (pinfunction "+IN_5") (pintype "bidirectional"))
      (node (ref "OP5") (pin "3") (pinfunction "+IN_3") (pintype "bidirectional"))
      (node (ref "OP5") (pin "5") (pinfunction "+IN_5") (pintype "bidirectional"))
      (node (ref "R11") (pin "1") (pinfunction "1_1") (pintype "passive"))
    )
    (net (code "55") (name "T_OUT0") (class "Default")
      (node (ref "J1") (pin "6") (pinfunction "P$6_6") (pintype "bidirectional"))
      (node (ref "Q10") (pin "3") (pinfunction "D1_3") (pintype "passive"))
    )
    (net (code "56") (name "T_OUT1") (class "Default")
      (node (ref "J1") (pin "8") (pinfunction "P$8_8") (pintype "bidirectional"))
      (node (ref "Q12") (pin "3") (pinfunction "D1_3") (pintype "passive"))
    )
    (net (code "57") (name "T_OUT2") (class "Default")
      (node (ref "J1") (pin "10") (pinfunction "P$10_10") (pintype "bidirectional"))
      (node (ref "Q26") (pin "3") (pinfunction "D1_3") (pintype "passive"))
    )
    (net (code "58") (name "T_OUT3") (class "Default")
      (node (ref "J1") (pin "12") (pinfunction "P$12_12") (pintype "bidirectional"))
      (node (ref "Q28") (pin "3") (pinfunction "D1_3") (pintype "passive"))
    )
    (net (code "59") (name "T_OUT4") (class "Default")
      (node (ref "J1") (pin "14") (pinfunction "P$14_14") (pintype "bidirectional"))
      (node (ref "Q38") (pin "3") (pinfunction "D1_3") (pintype "passive"))
    )
    (net (code "60") (name "T_OUT5") (class "Default")
      (node (ref "J1") (pin "16") (pinfunction "P$16_16") (pintype "bidirectional"))
      (node (ref "Q40") (pin "3") (pinfunction "D1_3") (pintype "passive"))
    )
    (net (code "61") (name "T_OUT6") (class "Default")
      (node (ref "J1") (pin "18") (pinfunction "P$18_18") (pintype "bidirectional"))
      (node (ref "Q14") (pin "3") (pinfunction "D1_3") (pintype "passive"))
    )
    (net (code "62") (name "T_OUT7") (class "Default")
      (node (ref "J1") (pin "20") (pinfunction "P$20_20") (pintype "bidirectional"))
      (node (ref "Q16") (pin "3") (pinfunction "D1_3") (pintype "passive"))
    )
    (net (code "63") (name "T_OUT8") (class "Default")
      (node (ref "J1") (pin "22") (pinfunction "P$22_22") (pintype "bidirectional"))
      (node (ref "Q30") (pin "3") (pinfunction "D1_3") (pintype "passive"))
    )
    (net (code "64") (name "T_OUT9") (class "Default")
      (node (ref "J1") (pin "24") (pinfunction "P$24_24") (pintype "bidirectional"))
      (node (ref "Q32") (pin "3") (pinfunction "D1_3") (pintype "passive"))
    )
    (net (code "65") (name "V+") (class "Default")
      (node (ref "C5") (pin "1") (pinfunction "1_1") (pintype "passive"))
      (node (ref "D1") (pin "A") (pinfunction "A_A") (pintype "passive"))
      (node (ref "D3") (pin "C") (pinfunction "K_C") (pintype "passive"))
      (node (ref "J1") (pin "3") (pinfunction "P$3_3") (pintype "bidirectional"))
      (node (ref "OP1") (pin "8") (pinfunction "V+_8") (pintype "power_in"))
      (node (ref "OP2") (pin "8") (pinfunction "V+_8") (pintype "power_in"))
      (node (ref "OP3") (pin "8") (pinfunction "V+_8") (pintype "power_in"))
      (node (ref "OP4") (pin "8") (pinfunction "V+_8") (pintype "power_in"))
      (node (ref "OP5") (pin "8") (pinfunction "V+_8") (pintype "power_in"))
      (node (ref "R12") (pin "1") (pinfunction "1_1") (pintype "passive"))
      (node (ref "R14") (pin "1") (pinfunction "1_1") (pintype "passive"))
      (node (ref "VREG2") (pin "3") (pinfunction "VOUT_3") (pintype "power_in"))
    )
    (net (code "66") (name "V-") (class "Default")
      (node (ref "C6") (pin "2") (pinfunction "2_2") (pintype "passive"))
      (node (ref "D2") (pin "C") (pinfunction "K_C") (pintype "passive"))
      (node (ref "D4") (pin "A") (pinfunction "A_A") (pintype "passive"))
      (node (ref "JP2") (pin "2") (pinfunction "2_2") (pintype "passive"))
      (node (ref "LED2") (pin "C") (pinfunction "C_C") (pintype "passive"))
      (node (ref "OP1") (pin "4") (pinfunction "V-_4") (pintype "power_in"))
      (node (ref "OP2") (pin "4") (pinfunction "V-_4") (pintype "power_in"))
      (node (ref "OP3") (pin "4") (pinfunction "V-_4") (pintype "power_in"))
      (node (ref "OP4") (pin "4") (pinfunction "V-_4") (pintype "power_in"))
      (node (ref "OP5") (pin "4") (pinfunction "V-_4") (pintype "power_in"))
      (node (ref "VREG1") (pin "3") (pinfunction "VOUT_3") (pintype "power_in"))
    )
  )
)
